# micro.net
KiCad netlist of a schematic drawn in Altium Designer
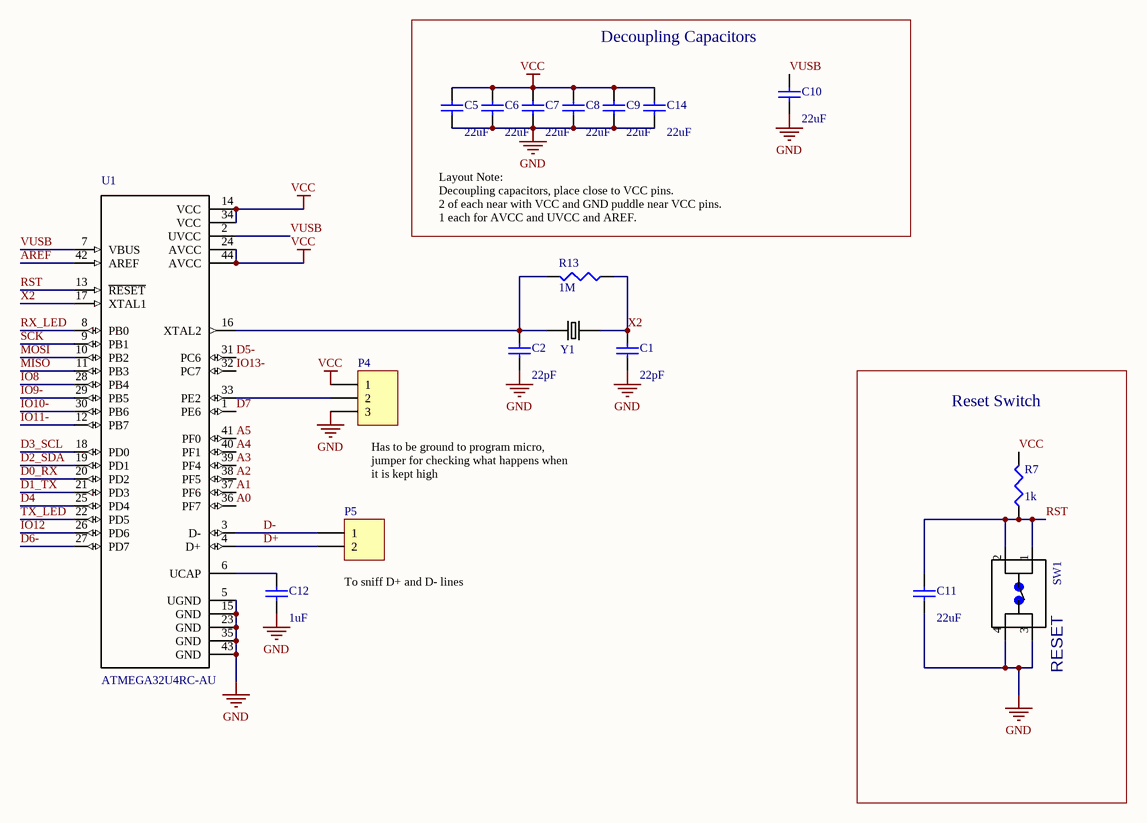
[diagram p0: micro.SchDoc]

(export (version "E")
  (design (tool "Eeschema 10.0.6"))
  (components
    (comp (ref "C1")
      (value "22pF")
      (footprint "C1206")
      (description "Capacitor (Semiconductor SIM Model)")
      (fields
        (field (name "DIGIKEYPARTNO") "732-7867-1-ND")
        (field (name "Comment") "Cap Semi")
        (field (name "PUBLISHER") "Altium Limited")
      )
      (libsource (lib "Miscellaneous Devices") (part "Cap Semi"))
    )
    (comp (ref "C2")
      (value "22pF")
      (footprint "C1206")
      (description "Capacitor (Semiconductor SIM Model)")
      (fields
        (field (name "DIGIKEYPARTNO") "732-7867-1-ND")
        (field (name "Comment") "Cap Semi")
        (field (name "PUBLISHER") "Altium Limited")
      )
      (libsource (lib "Miscellaneous Devices") (part "Cap Semi"))
    )
    (comp (ref "C5")
      (value "22uF")
      (footprint "C1206")
      (description "Capacitor (Semiconductor SIM Model)")
      (fields
        (field (name "DIGIKEYPARTNO") "1276-3300-1-ND")
        (field (name "Comment") "Cap Semi")
        (field (name "PUBLISHER") "Altium Limited")
      )
      (libsource (lib "Miscellaneous Devices") (part "Cap Semi"))
    )
    (comp (ref "C6")
      (value "22uF")
      (footprint "C1206")
      (description "Capacitor (Semiconductor SIM Model)")
      (fields
        (field (name "DIGIKEYPARTNO") "1276-3300-1-ND")
        (field (name "Comment") "Cap Semi")
        (field (name "PUBLISHER") "Altium Limited")
      )
      (libsource (lib "Miscellaneous Devices") (part "Cap Semi"))
    )
    (comp (ref "C7")
      (value "22uF")
      (footprint "C1206")
      (description "Capacitor (Semiconductor SIM Model)")
      (fields
        (field (name "DIGIKEYPARTNO") "1276-3300-1-ND")
        (field (name "Comment") "Cap Semi")
        (field (name "PUBLISHER") "Altium Limited")
      )
      (libsource (lib "Miscellaneous Devices") (part "Cap Semi"))
    )
    (comp (ref "C8")
      (value "22uF")
      (footprint "C1206")
      (description "Capacitor (Semiconductor SIM Model)")
      (fields
        (field (name "DIGIKEYPARTNO") "1276-3300-1-ND")
        (field (name "Comment") "Cap Semi")
        (field (name "PUBLISHER") "Altium Limited")
      )
      (libsource (lib "Miscellaneous Devices") (part "Cap Semi"))
    )
    (comp (ref "C9")
      (value "22uF")
      (footprint "C1206")
      (description "Capacitor (Semiconductor SIM Model)")
      (fields
        (field (name "DIGIKEYPARTNO") "1276-3300-1-ND")
        (field (name "Comment") "Cap Semi")
        (field (name "PUBLISHER") "Altium Limited")
      )
      (libsource (lib "Miscellaneous Devices") (part "Cap Semi"))
    )
    (comp (ref "C10")
      (value "22uF")
      (footprint "C1206")
      (description "Capacitor (Semiconductor SIM Model)")
      (fields
        (field (name "DIGIKEYPARTNO") "1276-3300-1-ND")
        (field (name "Comment") "Cap Semi")
        (field (name "PUBLISHER") "Altium Limited")
      )
      (libsource (lib "Miscellaneous Devices") (part "Cap Semi"))
    )
    (comp (ref "C11")
      (value "22uF")
      (footprint "C1206")
      (description "Capacitor (Semiconductor SIM Model)")
      (fields (field (name "Comment") "Cap Semi") (field (name "PUBLISHER") "Altium Limited"))
      (libsource (lib "Miscellaneous Devices") (part "Cap Semi"))
    )
    (comp (ref "C12")
      (value "1uF")
      (footprint "C1206")
      (description "Capacitor (Semiconductor SIM Model)")
      (fields (field (name "Comment") "Cap Semi") (field (name "PUBLISHER") "Altium Limited"))
      (libsource (lib "Miscellaneous Devices") (part "Cap Semi"))
    )
    (comp (ref "C14")
      (value "22uF")
      (footprint "C1206")
      (description "Capacitor (Semiconductor SIM Model)")
      (fields
        (field (name "DIGIKEYPARTNO") "1276-3300-1-ND")
        (field (name "Comment") "Cap Semi")
        (field (name "PUBLISHER") "Altium Limited")
      )
      (libsource (lib "Miscellaneous Devices") (part "Cap Semi"))
    )
    (comp (ref "P4")
      (value "+HWB-")
      (footprint "HDR1X3")
      (description "Header, 3-Pin")
      (fields (field (name "PUBLISHER") "Altium Limited"))
      (libsource (lib "Miscellaneous Connectors") (part "Header 3"))
    )
    (comp (ref "P5")
      (value "+USB_D-")
      (footprint "HDR1X2")
      (description "Header, 2-Pin")
      (fields (field (name "PUBLISHER") "Altium Limited"))
      (libsource (lib "Miscellaneous Connectors") (part "Header 2"))
    )
    (comp (ref "R7")
      (value "1k")
      (footprint "C1206")
      (description "Resistor")
      (fields (field (name "Comment") "Res3") (field (name "PUBLISHER") "Altium Limited"))
      (libsource (lib "Miscellaneous Devices") (part "Res3"))
    )
    (comp (ref "R13")
      (value "1M")
      (footprint "C1206")
      (description "Resistor")
      (fields (field (name "Comment") "Res3") (field (name "PUBLISHER") "Altium Limited"))
      (libsource (lib "Miscellaneous Devices") (part "Res3"))
    )
    (comp (ref "SW1")
      (value "RESET")
      (footprint "*TE_FSM4JSMA")
      (description "FSM4JSMA=SMT,TACTILE,PB SWITCH")
      (fields (field (name "MF") "TE Connectivity") (field (name "MP") "FSM4JSMA"))
      (libsource (lib "FSM4JSMA") (part "FSM4JSMA"))
    )
    (comp (ref "U1")
      (value "ATMEGA32U4RC-AU")
      (footprint "*QFP80P1200X1200X120-44N")
      (description "MCU 8-bit ATmega AVR RISC 32KB Flash 3.3V/5V 44-Pin TQFP")
      (fields (field (name "MP") "ATMEGA32U4-AU") (field (name "MF") "Microchip"))
      (libsource (lib "ATMEGA32U4-AU") (part "ATMEGA32U4-AU"))
    )
    (comp (ref "Y1")
      (value "ECS-35-17-5PX-TR")
      (footprint "*XTAL_ECS-35-17-5PX-TR")
      (description "Crystal 3.579545MHz Â±30ppm _Tol_ Â±50ppm _Stability_ 17pF FUND 150Ohm 2-Pin HC-49/USX SMD T/R")
      (fields (field (name "MF") "ECS Inc."))
      (libsource (lib "ECS-35-17-5PX-TR") (part "ECS-35-17-5PX-TR"))
    )
  )
  (nets
    (net (code "1") (name "/A0") (class "Default")
      (node (ref "U1") (pin "36") (pinfunction "PF7_36") (pintype "bidirectional"))
    )
    (net (code "2") (name "/A1") (class "Default")
      (node (ref "U1") (pin "37") (pinfunction "PF6_37") (pintype "bidirectional"))
    )
    (net (code "3") (name "/A2") (class "Default")
      (node (ref "U1") (pin "38") (pinfunction "PF5_38") (pintype "bidirectional"))
    )
    (net (code "4") (name "/A3") (class "Default")
      (node (ref "U1") (pin "39") (pinfunction "PF4_39") (pintype "bidirectional"))
    )
    (net (code "5") (name "/A4") (class "Default")
      (node (ref "U1") (pin "40") (pinfunction "PF1_40") (pintype "bidirectional"))
    )
    (net (code "6") (name "/A5") (class "Default")
      (node (ref "U1") (pin "41") (pinfunction "PF0_41") (pintype "bidirectional"))
    )
    (net (code "7") (name "/AREF") (class "Default")
      (node (ref "U1") (pin "42") (pinfunction "AREF_42") (pintype "input"))
    )
    (net (code "8") (name "/D+") (class "Default")
      (node (ref "P5") (pin "2") (pinfunction "2_2") (pintype "passive"))
      (node (ref "U1") (pin "4") (pinfunction "D+_4") (pintype "bidirectional"))
    )
    (net (code "9") (name "/D-") (class "Default")
      (node (ref "P5") (pin "1") (pinfunction "1_1") (pintype "passive"))
      (node (ref "U1") (pin "3") (pinfunction "D-_3") (pintype "bidirectional"))
    )
    (net (code "10") (name "/D0_RX") (class "Default")
      (node (ref "U1") (pin "20") (pinfunction "PD2_20") (pintype "bidirectional"))
    )
    (net (code "11") (name "/D1_TX") (class "Default")
      (node (ref "U1") (pin "21") (pinfunction "PD3_21") (pintype "bidirectional"))
    )
    (net (code "12") (name "/D2_SDA") (class "Default")
      (node (ref "U1") (pin "19") (pinfunction "PD1_19") (pintype "bidirectional"))
    )
    (net (code "13") (name "/D3_SCL") (class "Default")
      (node (ref "U1") (pin "18") (pinfunction "PD0_18") (pintype "bidirectional"))
    )
    (net (code "14") (name "/D4") (class "Default")
      (node (ref "U1") (pin "25") (pinfunction "PD4_25") (pintype "bidirectional"))
    )
    (net (code "15") (name "/D5-") (class "Default")
      (node (ref "U1") (pin "31") (pinfunction "PC6_31") (pintype "bidirectional"))
    )
    (net (code "16") (name "/D6-") (class "Default")
      (node (ref "U1") (pin "27") (pinfunction "PD7_27") (pintype "bidirectional"))
    )
    (net (code "17") (name "/D7") (class "Default")
      (node (ref "U1") (pin "1") (pinfunction "PE6_1") (pintype "bidirectional"))
    )
    (net (code "18") (name "/IO8") (class "Default")
      (node (ref "U1") (pin "28") (pinfunction "PB4_28") (pintype "bidirectional"))
    )
    (net (code "19") (name "/IO9-") (class "Default")
      (node (ref "U1") (pin "29") (pinfunction "PB5_29") (pintype "bidirectional"))
    )
    (net (code "20") (name "/IO10-") (class "Default")
      (node (ref "U1") (pin "30") (pinfunction "PB6_30") (pintype "bidirectional"))
    )
    (net (code "21") (name "/IO11-") (class "Default")
      (node (ref "U1") (pin "12") (pinfunction "PB7_12") (pintype "bidirectional"))
    )
    (net (code "22") (name "/IO12") (class "Default")
      (node (ref "U1") (pin "26") (pinfunction "PD6_26") (pintype "bidirectional"))
    )
    (net (code "23") (name "/IO13-") (class "Default")
      (node (ref "U1") (pin "32") (pinfunction "PC7_32") (pintype "bidirectional"))
    )
    (net (code "24") (name "/MISO") (class "Default")
      (node (ref "U1") (pin "11") (pinfunction "PB3_11") (pintype "bidirectional"))
    )
    (net (code "25") (name "/MOSI") (class "Default")
      (node (ref "U1") (pin "10") (pinfunction "PB2_10") (pintype "bidirectional"))
    )
    (net (code "26") (name "/RST") (class "Default")
      (node (ref "C11") (pin "2") (pinfunction "2_2") (pintype "passive"))
      (node (ref "R7") (pin "1") (pinfunction "1_1") (pintype "passive"))
      (node (ref "SW1") (pin "1") (pinfunction "1_1") (pintype "passive"))
      (node (ref "SW1") (pin "2") (pinfunction "2_2") (pintype "passive"))
      (node (ref "U1") (pin "13") (pinfunction "~{RESET}_13") (pintype "input"))
    )
    (net (code "27") (name "/RX_LED") (class "Default")
      (node (ref "U1") (pin "8") (pinfunction "PB0_8") (pintype "bidirectional"))
    )
    (net (code "28") (name "/SCK") (class "Default")
      (node (ref "U1") (pin "9") (pinfunction "PB1_9") (pintype "bidirectional"))
    )
    (net (code "29") (name "/TX_LED") (class "Default")
      (node (ref "U1") (pin "22") (pinfunction "PD5_22") (pintype "bidirectional"))
    )
    (net (code "30") (name "/VUSB") (class "Default")
      (node (ref "C10") (pin "2") (pinfunction "2_2") (pintype "passive"))
      (node (ref "U1") (pin "2") (pinfunction "UVCC_2") (pintype "power_in"))
      (node (ref "U1") (pin "7") (pinfunction "VBUS_7") (pintype "input"))
    )
    (net (code "31") (name "/X2") (class "Default")
      (node (ref "C1") (pin "2") (pinfunction "2_2") (pintype "passive"))
      (node (ref "R13") (pin "1") (pinfunction "1_1") (pintype "passive"))
      (node (ref "U1") (pin "17") (pinfunction "XTAL1_17") (pintype "input"))
      (node (ref "Y1") (pin "2") (pinfunction "2_2") (pintype "passive"))
    )
    (net (code "32") (name "GND") (class "Default")
      (node (ref "C1") (pin "1") (pinfunction "1_1") (pintype "passive"))
      (node (ref "C10") (pin "1") (pinfunction "1_1") (pintype "passive"))
      (node (ref "C11") (pin "1") (pinfunction "1_1") (pintype "passive"))
      (node (ref "C12") (pin "1") (pinfunction "1_1") (pintype "passive"))
      (node (ref "C14") (pin "1") (pinfunction "1_1") (pintype "passive"))
      (node (ref "C2") (pin "1") (pinfunction "1_1") (pintype "passive"))
      (node (ref "C5") (pin "1") (pinfunction "1_1") (pintype "passive"))
      (node (ref "C6") (pin "1") (pinfunction "1_1") (pintype "passive"))
      (node (ref "C7") (pin "1") (pinfunction "1_1") (pintype "passive"))
      (node (ref "C8") (pin "1") (pinfunction "1_1") (pintype "passive"))
      (node (ref "C9") (pin "1") (pinfunction "1_1") (pintype "passive"))
      (node (ref "P4") (pin "3") (pinfunction "3_3") (pintype "passive"))
      (node (ref "SW1") (pin "3") (pinfunction "3_3") (pintype "passive"))
      (node (ref "SW1") (pin "4") (pinfunction "4_4") (pintype "passive"))
      (node (ref "U1") (pin "15") (pinfunction "GND_15") (pintype "power_in"))
      (node (ref "U1") (pin "23") (pinfunction "GND_23") (pintype "power_in"))
      (node (ref "U1") (pin "35") (pinfunction "GND_35") (pintype "power_in"))
      (node (ref "U1") (pin "43") (pinfunction "GND_43") (pintype "power_in"))
      (node (ref "U1") (pin "5") (pinfunction "UGND_5") (pintype "power_in"))
    )
    (net (code "33") (name "Net-(U1-PE2)") (class "Default")
      (node (ref "P4") (pin "2") (pinfunction "2_2") (pintype "passive"))
      (node (ref "U1") (pin "33") (pinfunction "PE2_33") (pintype "bidirectional"))
    )
    (net (code "34") (name "Net-(U1-UCAP)") (class "Default")
      (node (ref "C12") (pin "2") (pinfunction "2_2") (pintype "passive"))
      (node (ref "U1") (pin "6") (pinfunction "UCAP_6") (pintype "passive"))
    )
    (net (code "35") (name "Net-(U1-XTAL2)") (class "Default")
      (node (ref "C2") (pin "2") (pinfunction "2_2") (pintype "passive"))
      (node (ref "R13") (pin "2") (pinfunction "2_2") (pintype "passive"))
      (node (ref "U1") (pin "16") (pinfunction "XTAL2_16") (pintype "output"))
      (node (ref "Y1") (pin "1") (pinfunction "1_1") (pintype "passive"))
    )
    (net (code "36") (name "VCC") (class "Default")
      (node (ref "C14") (pin "2") (pinfunction "2_2") (pintype "passive"))
      (node (ref "C5") (pin "2") (pinfunction "2_2") (pintype "passive"))
      (node (ref "C6") (pin "2") (pinfunction "2_2") (pintype "passive"))
      (node (ref "C7") (pin "2") (pinfunction "2_2") (pintype "passive"))
      (node (ref "C8") (pin "2") (pinfunction "2_2") (pintype "passive"))
      (node (ref "C9") (pin "2") (pinfunction "2_2") (pintype "passive"))
      (node (ref "P4") (pin "1") (pinfunction "1_1") (pintype "passive"))
      (node (ref "R7") (pin "2") (pinfunction "2_2") (pintype "passive"))
      (node (ref "U1") (pin "14") (pinfunction "VCC_14") (pintype "power_in"))
      (node (ref "U1") (pin "24") (pinfunction "AVCC_24") (pintype "power_in"))
      (node (ref "U1") (pin "34") (pinfunction "VCC_34") (pintype "power_in"))
      (node (ref "U1") (pin "44") (pinfunction "AVCC_44") (pintype "power_in"))
    )
  )
)
